# PCB_-_MODULE.net
KiCad netlist of a schematic drawn in EAGLE
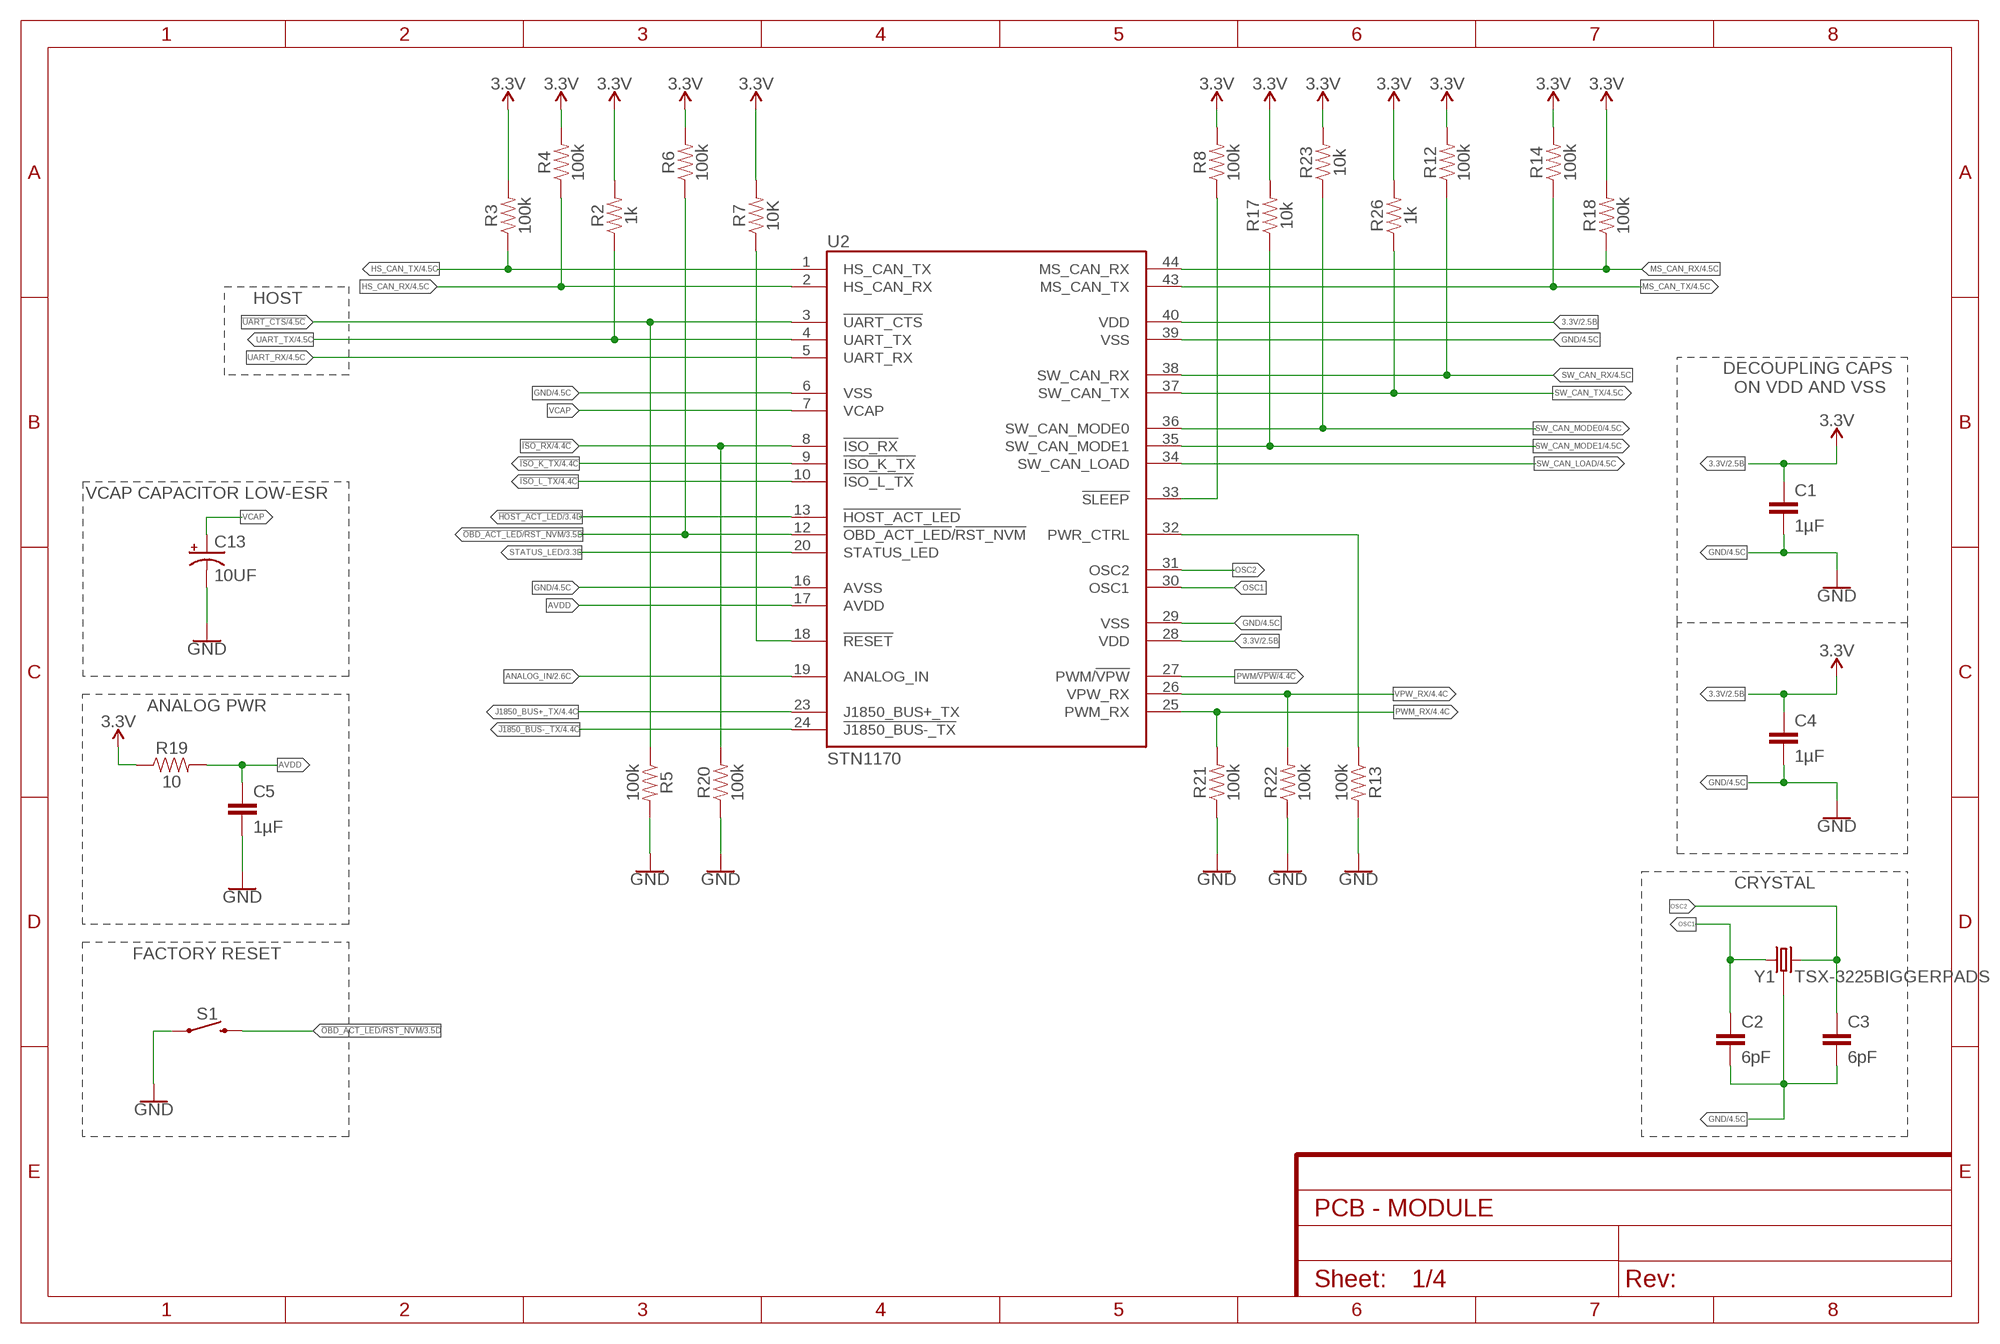
[diagram p0: schematic, sheet 1]
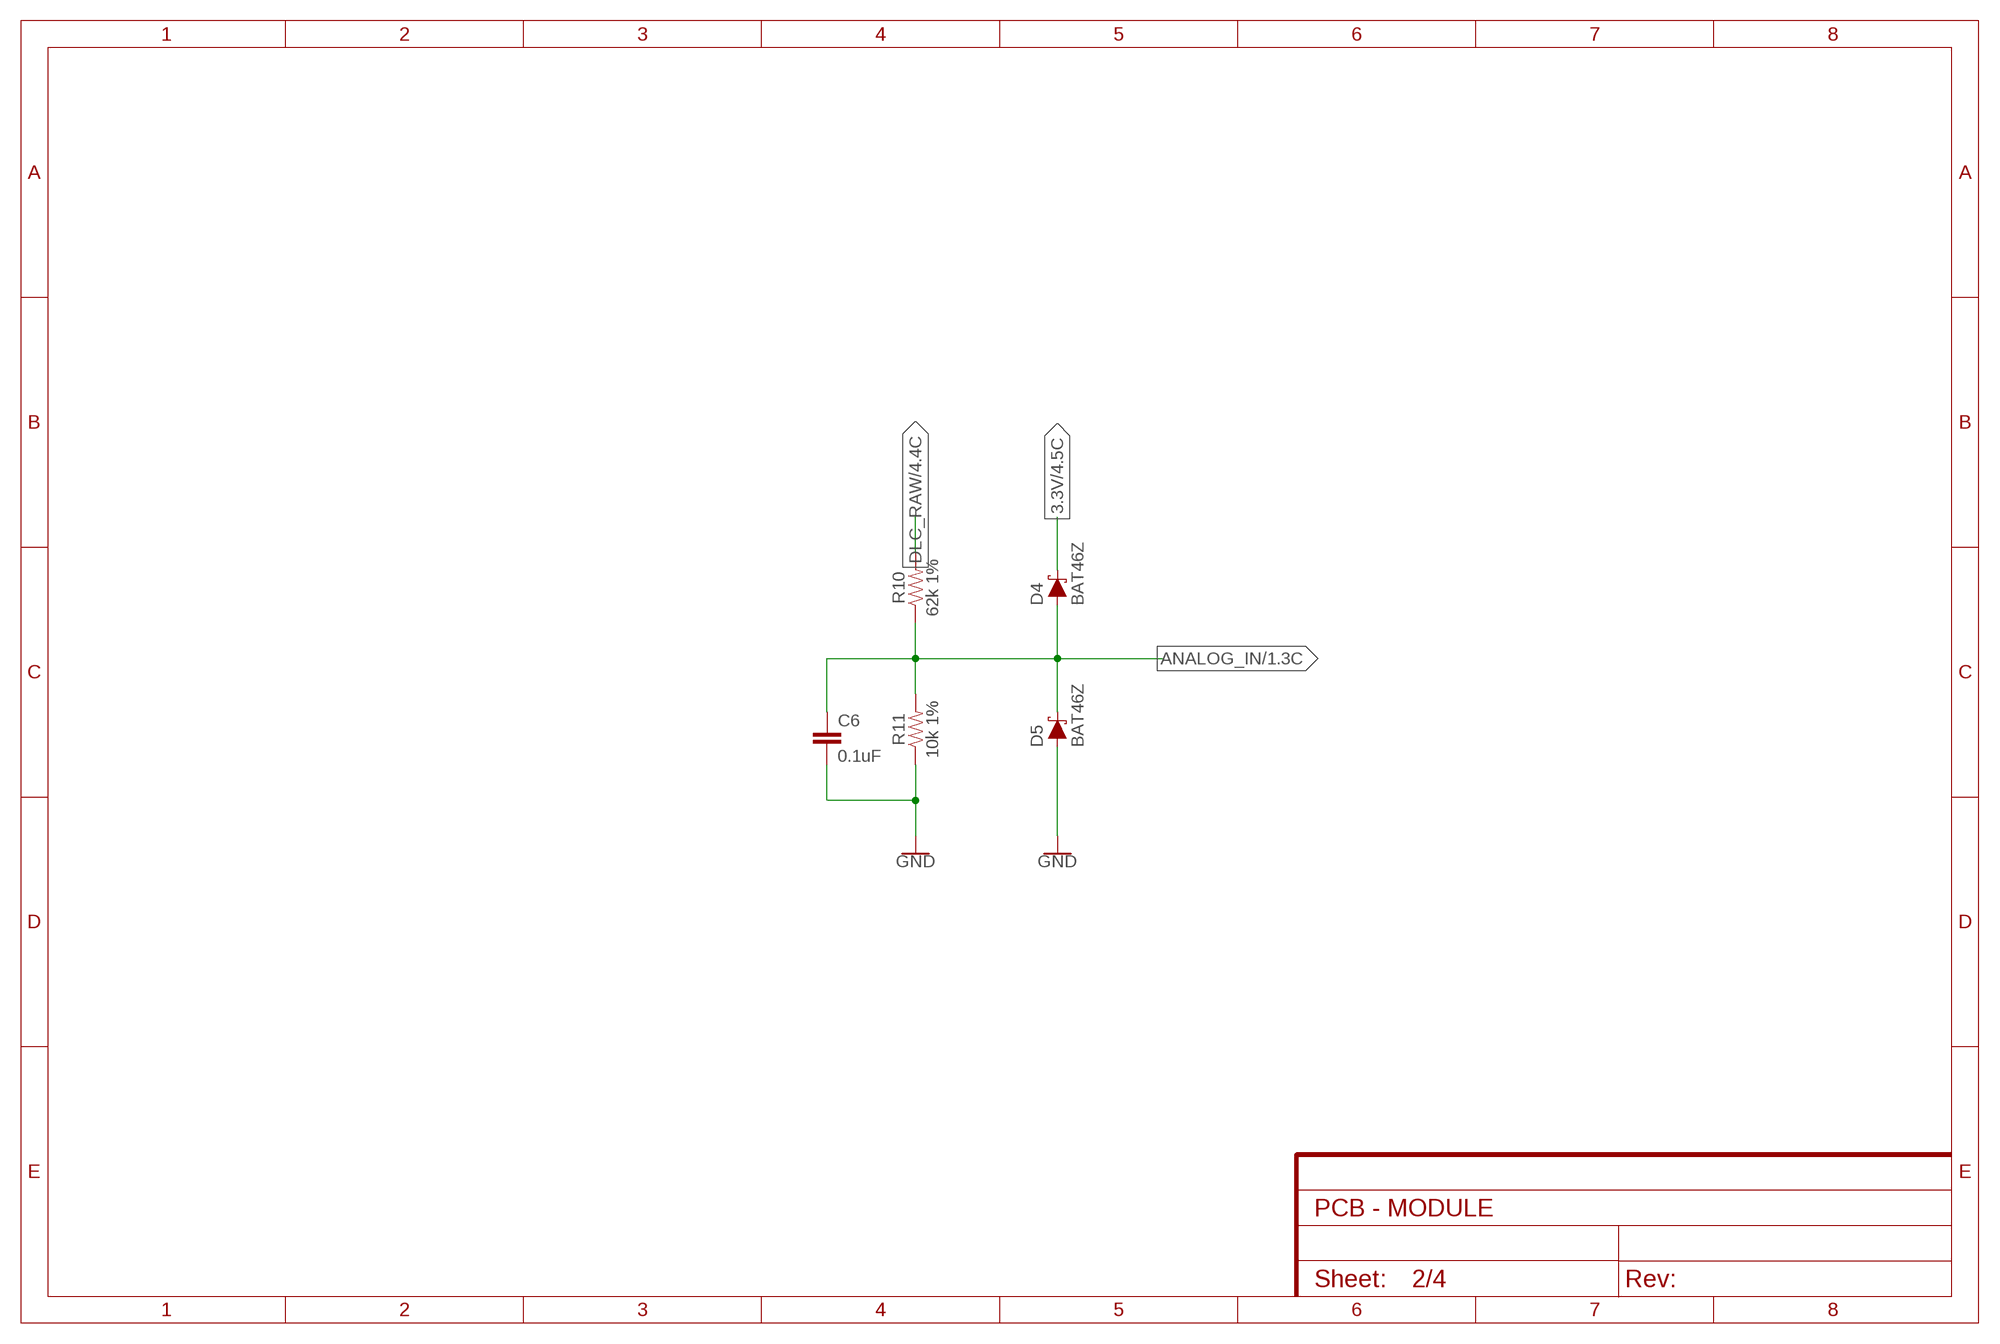
[diagram p1: schematic, sheet 2]
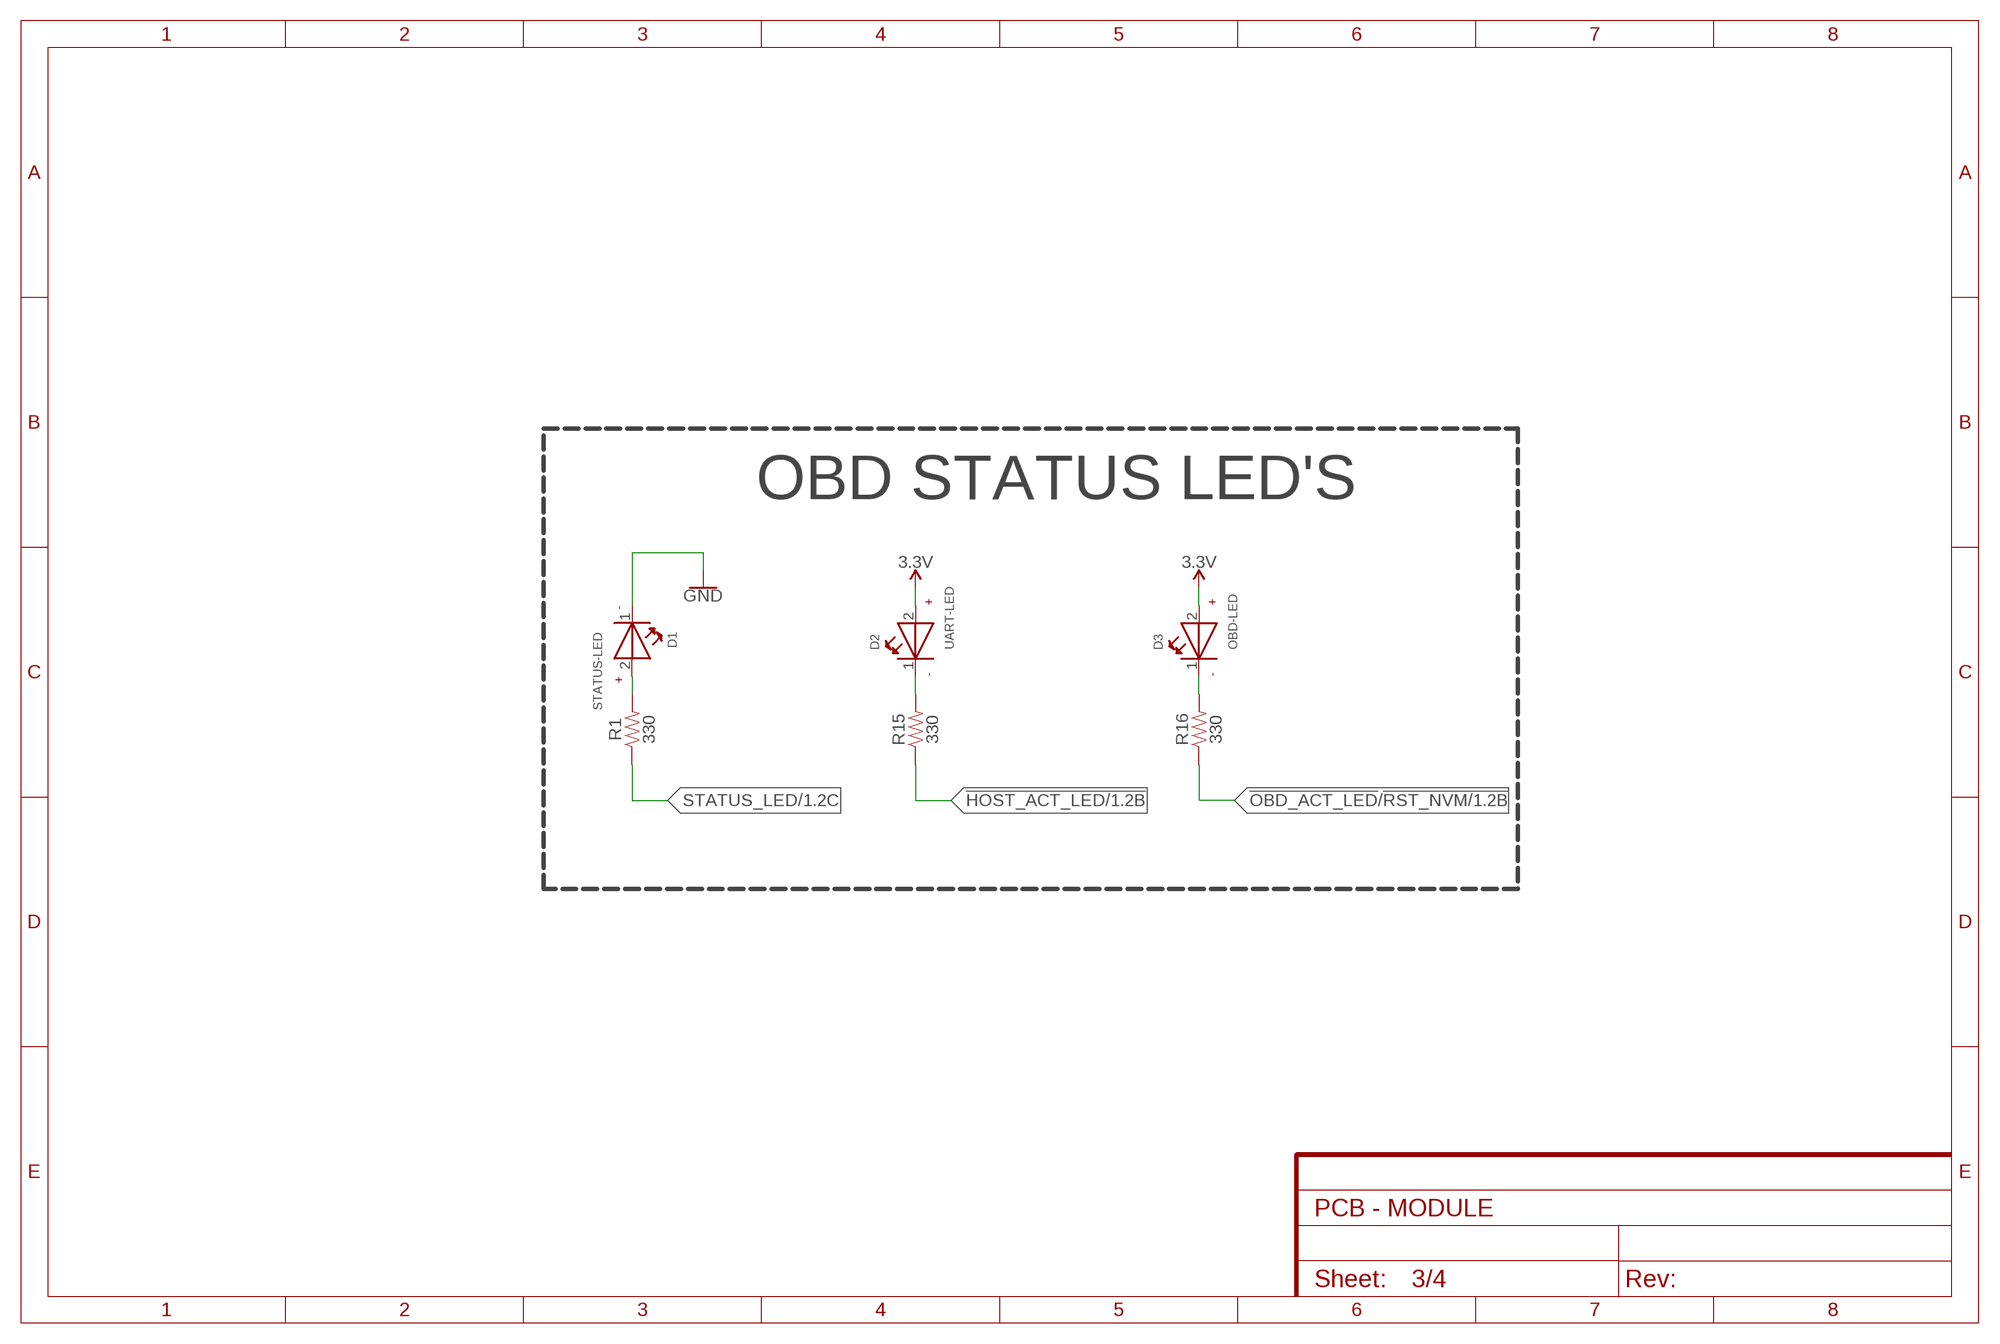
[diagram p2: schematic, sheet 3]
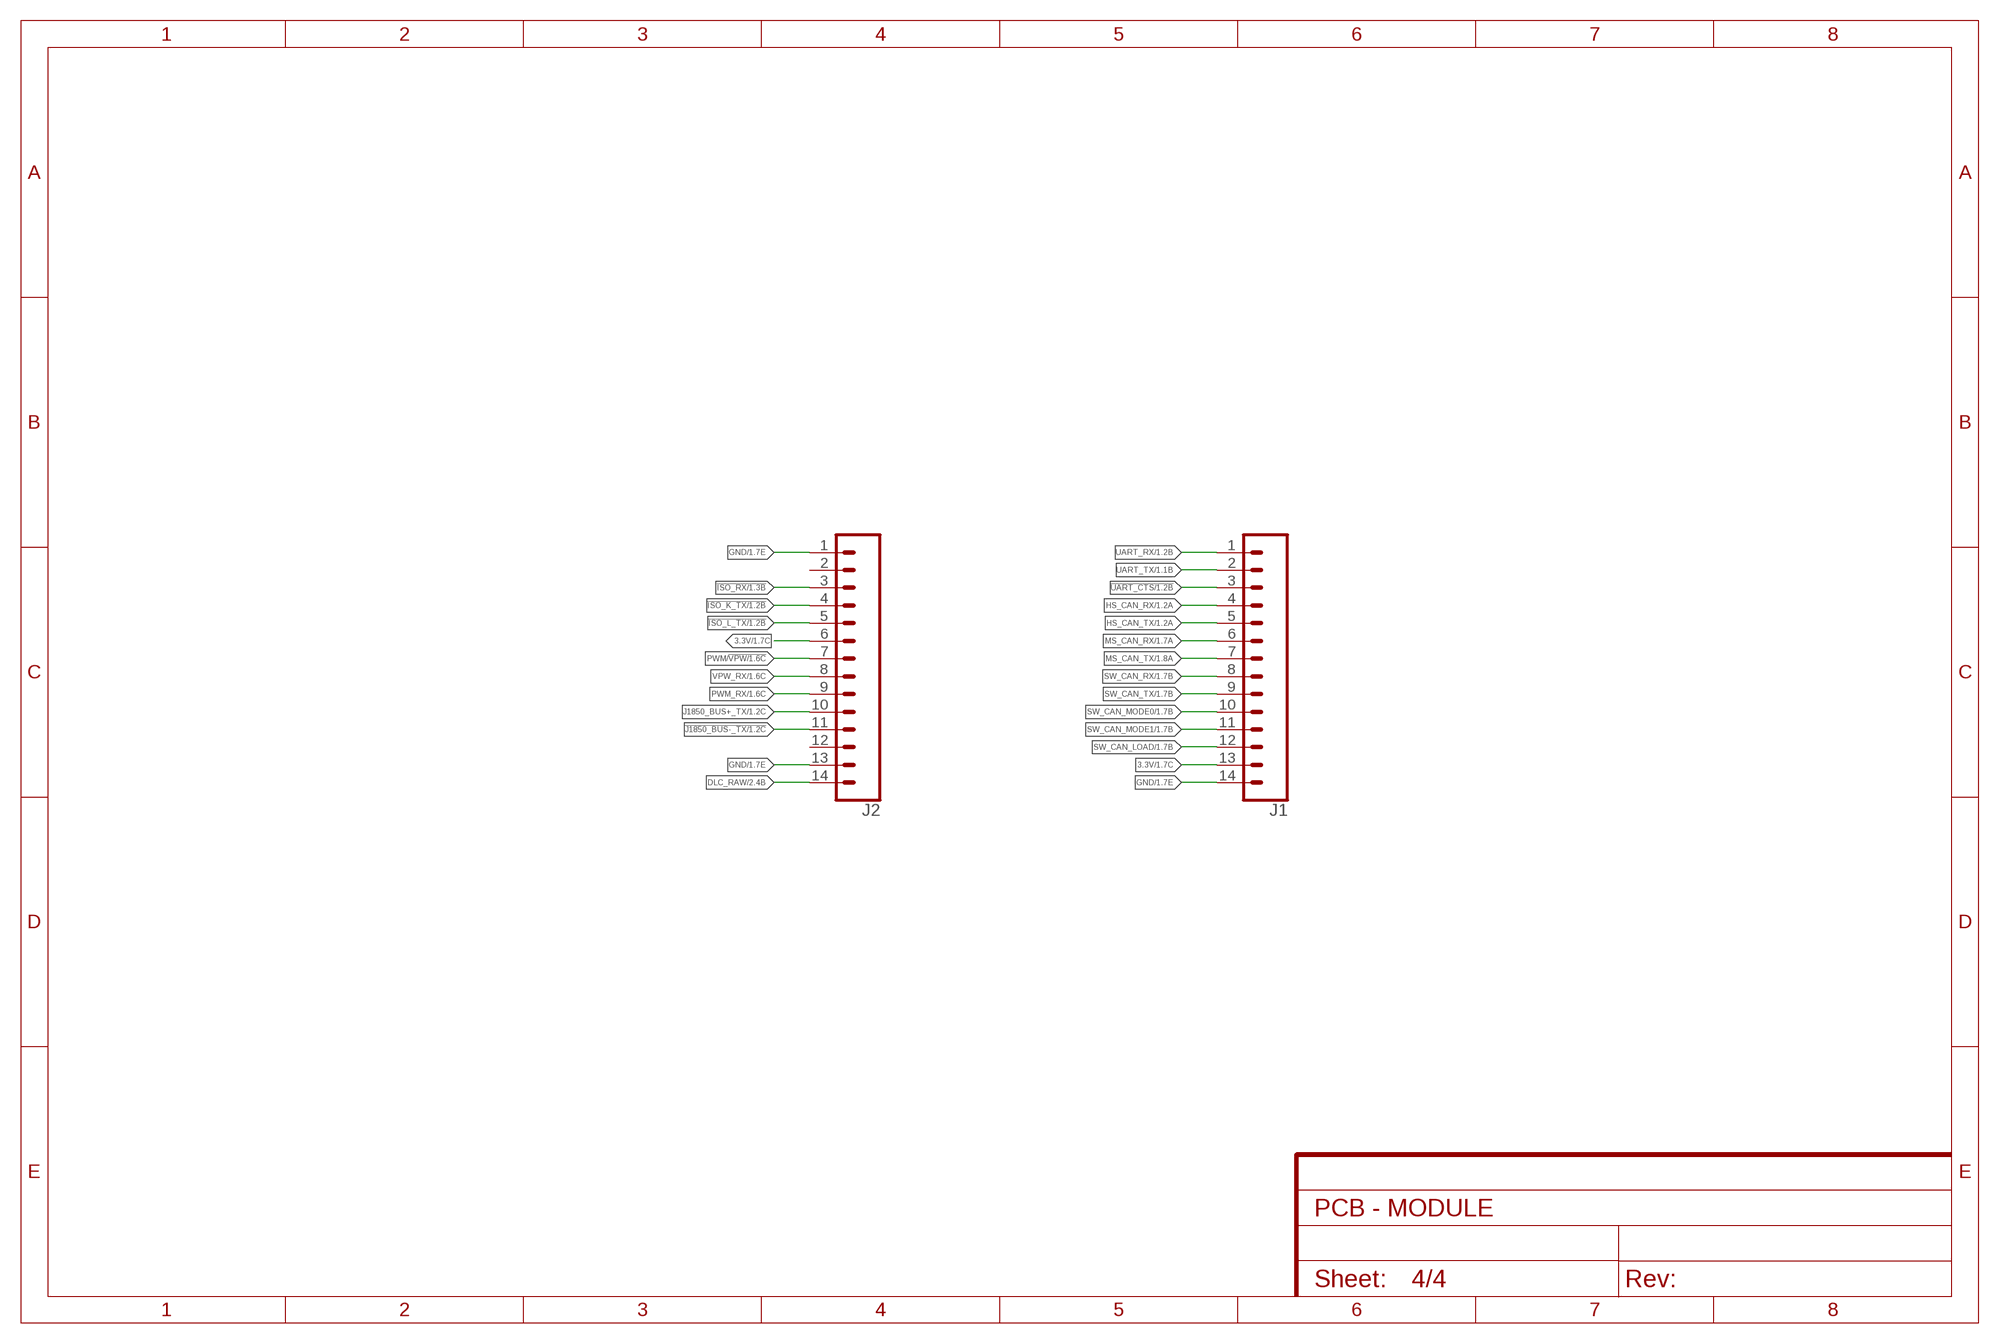
[diagram p3: schematic, sheet 4]

(export (version "E")
  (design (tool "Eeschema 10.0.6"))
  (components
    (comp (ref "C6")
      (value "0.1uF")
      (footprint "eagle-import:0805")
      (libsource (lib "eagle-import") (part "0.33UF/330NF-0805-50V-10%"))
    )
    (comp (ref "D4")
      (value "BAT46Z")
      (footprint "eagle-import:SOD-123")
      (libsource (lib "eagle-import") (part "BAT46Z"))
    )
    (comp (ref "D5")
      (value "BAT46Z")
      (footprint "eagle-import:SOD-123")
      (libsource (lib "eagle-import") (part "BAT46Z"))
    )
    (comp (ref "R10")
      (value "62k 1%")
      (footprint "eagle-import:0805")
      (libsource (lib "eagle-import") (part "0.75OHM-0805-1/4W-1%"))
    )
    (comp (ref "R11")
      (value "10k 1%")
      (footprint "eagle-import:0805")
      (libsource (lib "eagle-import") (part "0.75OHM-0805-1/4W-1%"))
    )
    (comp (ref "D1")
      (value "STATUS-LED")
      (footprint "eagle-import:WL-SMCW_1206")
      (libsource (lib "eagle-import") (part "WL-SMCW-150120RS75000-R"))
    )
    (comp (ref "D2")
      (value "UART-LED")
      (footprint "eagle-import:WL-SMCW_1206")
      (libsource (lib "eagle-import") (part "WL-SMCW-150120YS75000-Y"))
    )
    (comp (ref "D3")
      (value "OBD-LED")
      (footprint "eagle-import:WL-SMCW_1206")
      (libsource (lib "eagle-import") (part "WL-SMCW-150120GS75000-G"))
    )
    (comp (ref "R1")
      (value "330")
      (footprint "eagle-import:0805")
      (libsource (lib "eagle-import") (part "0.75OHM-0805-1/4W-1%"))
    )
    (comp (ref "R15")
      (value "330")
      (footprint "eagle-import:0805")
      (libsource (lib "eagle-import") (part "0.75OHM-0805-1/4W-1%"))
    )
    (comp (ref "R16")
      (value "330")
      (footprint "eagle-import:0805")
      (libsource (lib "eagle-import") (part "0.75OHM-0805-1/4W-1%"))
    )
    (comp (ref "J1")
      (value "CONN_14")
      (footprint "eagle-import:1X14")
      (libsource (lib "eagle-import") (part "CONN_14"))
    )
    (comp (ref "J2")
      (value "CONN_14")
      (footprint "eagle-import:1X14")
      (libsource (lib "eagle-import") (part "CONN_14"))
    )
    (comp (ref "C1")
      (value "1µF")
      (footprint "eagle-import:0805")
      (libsource (lib "eagle-import") (part "0.33UF/330NF-0805-50V-10%"))
    )
    (comp (ref "C2")
      (value "6pF")
      (footprint "eagle-import:0805")
      (libsource (lib "eagle-import") (part "0.33UF/330NF-0805-50V-10%"))
    )
    (comp (ref "C3")
      (value "6pF")
      (footprint "eagle-import:0805")
      (libsource (lib "eagle-import") (part "0.33UF/330NF-0805-50V-10%"))
    )
    (comp (ref "C4")
      (value "1µF")
      (footprint "eagle-import:0805")
      (libsource (lib "eagle-import") (part "0.33UF/330NF-0805-50V-10%"))
    )
    (comp (ref "C5")
      (value "1µF")
      (footprint "eagle-import:0805")
      (libsource (lib "eagle-import") (part "0.33UF/330NF-0805-50V-10%"))
    )
    (comp (ref "C13")
      (value "10UF")
      (footprint "eagle-import:1206")
      (libsource (lib "eagle-import") (part "10UF"))
    )
    (comp (ref "R2")
      (value "1k")
      (footprint "eagle-import:0805")
      (libsource (lib "eagle-import") (part "0.75OHM-0805-1/4W-1%"))
    )
    (comp (ref "R3")
      (value "100k")
      (footprint "eagle-import:0805")
      (libsource (lib "eagle-import") (part "0.75OHM-0805-1/4W-1%"))
    )
    (comp (ref "R4")
      (value "100k")
      (footprint "eagle-import:0805")
      (libsource (lib "eagle-import") (part "0.75OHM-0805-1/4W-1%"))
    )
    (comp (ref "R5")
      (value "100k")
      (footprint "eagle-import:0805")
      (libsource (lib "eagle-import") (part "0.75OHM-0805-1/4W-1%"))
    )
    (comp (ref "R6")
      (value "100k")
      (footprint "eagle-import:0805")
      (libsource (lib "eagle-import") (part "0.75OHM-0805-1/4W-1%"))
    )
    (comp (ref "R7")
      (value "10K")
      (footprint "eagle-import:0805")
      (libsource (lib "eagle-import") (part "0.75OHM-0805-1/4W-1%"))
    )
    (comp (ref "R8")
      (value "100k")
      (footprint "eagle-import:0805")
      (libsource (lib "eagle-import") (part "0.75OHM-0805-1/4W-1%"))
    )
    (comp (ref "R12")
      (value "100k")
      (footprint "eagle-import:0805")
      (libsource (lib "eagle-import") (part "0.75OHM-0805-1/4W-1%"))
    )
    (comp (ref "R13")
      (value "100k")
      (footprint "eagle-import:0805")
      (libsource (lib "eagle-import") (part "0.75OHM-0805-1/4W-1%"))
    )
    (comp (ref "R14")
      (value "100k")
      (footprint "eagle-import:0805")
      (libsource (lib "eagle-import") (part "0.75OHM-0805-1/4W-1%"))
    )
    (comp (ref "R17")
      (value "10k")
      (footprint "eagle-import:0805")
      (libsource (lib "eagle-import") (part "0.75OHM-0805-1/4W-1%"))
    )
    (comp (ref "R18")
      (value "100k")
      (footprint "eagle-import:0805")
      (libsource (lib "eagle-import") (part "0.75OHM-0805-1/4W-1%"))
    )
    (comp (ref "R19")
      (value "10")
      (footprint "eagle-import:0805")
      (libsource (lib "eagle-import") (part "0.75OHM-0805-1/4W-1%"))
    )
    (comp (ref "R20")
      (value "100k")
      (footprint "eagle-import:0805")
      (libsource (lib "eagle-import") (part "0.75OHM-0805-1/4W-1%"))
    )
    (comp (ref "R21")
      (value "100k")
      (footprint "eagle-import:0805")
      (libsource (lib "eagle-import") (part "0.75OHM-0805-1/4W-1%"))
    )
    (comp (ref "R22")
      (value "100k")
      (footprint "eagle-import:0805")
      (libsource (lib "eagle-import") (part "0.75OHM-0805-1/4W-1%"))
    )
    (comp (ref "R23")
      (value "10k")
      (footprint "eagle-import:0805")
      (libsource (lib "eagle-import") (part "0.75OHM-0805-1/4W-1%"))
    )
    (comp (ref "R26")
      (value "1k")
      (footprint "eagle-import:0805")
      (libsource (lib "eagle-import") (part "0.75OHM-0805-1/4W-1%"))
    )
    (comp (ref "S1")
      (value "B3U")
      (footprint "eagle-import:B3U-WO-GT-WO-B")
      (libsource (lib "eagle-import") (part "B3U"))
    )
    (comp (ref "U2")
      (value "STN1170")
      (footprint "eagle-import:TQFP44")
      (libsource (lib "eagle-import") (part "STN1170"))
    )
    (comp (ref "Y1")
      (value "TSX-3225BIGGERPADS")
      (footprint "eagle-import:TSX-3225-SOLDERING-IRON")
      (libsource (lib "eagle-import") (part "TSX-3225BIGGERPADS"))
    )
  )
  (nets
    (net (code "1") (name "3.3V") (class "Default")
      (node (ref "C1") (pin "1") (pinfunction "1_1") (pintype "passive"))
      (node (ref "C4") (pin "1") (pinfunction "1_1") (pintype "passive"))
      (node (ref "D2") (pin "2") (pinfunction "+_2") (pintype "passive"))
      (node (ref "D3") (pin "2") (pinfunction "+_2") (pintype "passive"))
      (node (ref "D4") (pin "C") (pinfunction "C_C") (pintype "passive"))
      (node (ref "J1") (pin "13") (pinfunction "13_13") (pintype "passive"))
      (node (ref "J2") (pin "6") (pinfunction "6_6") (pintype "passive"))
      (node (ref "R12") (pin "2") (pinfunction "2_2") (pintype "passive"))
      (node (ref "R14") (pin "2") (pinfunction "2_2") (pintype "passive"))
      (node (ref "R17") (pin "2") (pinfunction "2_2") (pintype "passive"))
      (node (ref "R18") (pin "2") (pinfunction "2_2") (pintype "passive"))
      (node (ref "R19") (pin "1") (pinfunction "1_1") (pintype "passive"))
      (node (ref "R2") (pin "2") (pinfunction "2_2") (pintype "passive"))
      (node (ref "R23") (pin "2") (pinfunction "2_2") (pintype "passive"))
      (node (ref "R26") (pin "2") (pinfunction "2_2") (pintype "passive"))
      (node (ref "R3") (pin "2") (pinfunction "2_2") (pintype "passive"))
      (node (ref "R4") (pin "2") (pinfunction "2_2") (pintype "passive"))
      (node (ref "R6") (pin "2") (pinfunction "2_2") (pintype "passive"))
      (node (ref "R7") (pin "2") (pinfunction "2_2") (pintype "passive"))
      (node (ref "R8") (pin "2") (pinfunction "2_2") (pintype "passive"))
      (node (ref "U2") (pin "28") (pinfunction "VDD_28") (pintype "power_in"))
      (node (ref "U2") (pin "40") (pinfunction "VDD_40") (pintype "power_in"))
    )
    (net (code "2") (name "ANALOG_IN") (class "Default")
      (node (ref "C6") (pin "1") (pinfunction "1_1") (pintype "passive"))
      (node (ref "D4") (pin "A") (pinfunction "A_A") (pintype "passive"))
      (node (ref "D5") (pin "C") (pinfunction "C_C") (pintype "passive"))
      (node (ref "R10") (pin "1") (pinfunction "1_1") (pintype "passive"))
      (node (ref "R11") (pin "2") (pinfunction "2_2") (pintype "passive"))
      (node (ref "U2") (pin "19") (pinfunction "ANALOG_IN_19") (pintype "input"))
    )
    (net (code "3") (name "AVDD") (class "Default")
      (node (ref "C5") (pin "1") (pinfunction "1_1") (pintype "passive"))
      (node (ref "R19") (pin "2") (pinfunction "2_2") (pintype "passive"))
      (node (ref "U2") (pin "17") (pinfunction "AVDD_17") (pintype "power_in"))
    )
    (net (code "4") (name "DLC_RAW") (class "Default")
      (node (ref "J2") (pin "14") (pinfunction "14_14") (pintype "passive"))
      (node (ref "R10") (pin "2") (pinfunction "2_2") (pintype "passive"))
    )
    (net (code "5") (name "GND") (class "Default")
      (node (ref "C1") (pin "2") (pinfunction "2_2") (pintype "passive"))
      (node (ref "C13") (pin "2") (pinfunction "-_2") (pintype "passive"))
      (node (ref "C2") (pin "2") (pinfunction "2_2") (pintype "passive"))
      (node (ref "C3") (pin "2") (pinfunction "2_2") (pintype "passive"))
      (node (ref "C4") (pin "2") (pinfunction "2_2") (pintype "passive"))
      (node (ref "C5") (pin "2") (pinfunction "2_2") (pintype "passive"))
      (node (ref "C6") (pin "2") (pinfunction "2_2") (pintype "passive"))
      (node (ref "D1") (pin "1") (pinfunction "-_1") (pintype "passive"))
      (node (ref "D5") (pin "A") (pinfunction "A_A") (pintype "passive"))
      (node (ref "J1") (pin "14") (pinfunction "14_14") (pintype "passive"))
      (node (ref "J2") (pin "1") (pinfunction "1_1") (pintype "passive"))
      (node (ref "J2") (pin "13") (pinfunction "13_13") (pintype "passive"))
      (node (ref "R11") (pin "1") (pinfunction "1_1") (pintype "passive"))
      (node (ref "R13") (pin "2") (pinfunction "2_2") (pintype "passive"))
      (node (ref "R20") (pin "1") (pinfunction "1_1") (pintype "passive"))
      (node (ref "R21") (pin "1") (pinfunction "1_1") (pintype "passive"))
      (node (ref "R22") (pin "1") (pinfunction "1_1") (pintype "passive"))
      (node (ref "R5") (pin "2") (pinfunction "2_2") (pintype "passive"))
      (node (ref "S1") (pin "1") (pinfunction "1_1") (pintype "passive"))
      (node (ref "U2") (pin "16") (pinfunction "AVSS_16") (pintype "power_in"))
      (node (ref "U2") (pin "29") (pinfunction "VSS_29") (pintype "power_in"))
      (node (ref "U2") (pin "39") (pinfunction "VSS_39") (pintype "power_in"))
      (node (ref "U2") (pin "6") (pinfunction "VSS_6") (pintype "power_in"))
      (node (ref "Y1") (pin "2") (pinfunction "3_2") (pintype "passive"))
      (node (ref "Y1") (pin "4") (pinfunction "3_4") (pintype "passive"))
    )
    (net (code "6") (name "HS_CAN_RX") (class "Default")
      (node (ref "J1") (pin "4") (pinfunction "4_4") (pintype "passive"))
      (node (ref "R4") (pin "1") (pinfunction "1_1") (pintype "passive"))
      (node (ref "U2") (pin "2") (pinfunction "HS_CAN_RX_2") (pintype "input"))
    )
    (net (code "7") (name "HS_CAN_TX") (class "Default")
      (node (ref "J1") (pin "5") (pinfunction "5_5") (pintype "passive"))
      (node (ref "R3") (pin "1") (pinfunction "1_1") (pintype "passive"))
      (node (ref "U2") (pin "1") (pinfunction "HS_CAN_TX_1") (pintype "input"))
    )
    (net (code "8") (name "J1850_BUS+_TX") (class "Default")
      (node (ref "J2") (pin "10") (pinfunction "10_10") (pintype "passive"))
      (node (ref "U2") (pin "23") (pinfunction "J1850_BUS+_TX_23") (pintype "output"))
    )
    (net (code "9") (name "MS_CAN_RX") (class "Default")
      (node (ref "J1") (pin "6") (pinfunction "6_6") (pintype "passive"))
      (node (ref "R18") (pin "1") (pinfunction "1_1") (pintype "passive"))
      (node (ref "U2") (pin "44") (pinfunction "MS_CAN_RX_44") (pintype "input"))
    )
    (net (code "10") (name "MS_CAN_TX") (class "Default")
      (node (ref "J1") (pin "7") (pinfunction "7_7") (pintype "passive"))
      (node (ref "R14") (pin "1") (pinfunction "1_1") (pintype "passive"))
      (node (ref "U2") (pin "43") (pinfunction "MS_CAN_TX_43") (pintype "output"))
    )
    (net (code "11") (name "Net-(D1-+)") (class "Default")
      (node (ref "D1") (pin "2") (pinfunction "+_2") (pintype "passive"))
      (node (ref "R1") (pin "2") (pinfunction "2_2") (pintype "passive"))
    )
    (net (code "12") (name "Net-(D2--)") (class "Default")
      (node (ref "D2") (pin "1") (pinfunction "-_1") (pintype "passive"))
      (node (ref "R15") (pin "2") (pinfunction "2_2") (pintype "passive"))
    )
    (net (code "13") (name "Net-(D3--)") (class "Default")
      (node (ref "D3") (pin "1") (pinfunction "-_1") (pintype "passive"))
      (node (ref "R16") (pin "2") (pinfunction "2_2") (pintype "passive"))
    )
    (net (code "14") (name "Net-(U2-PWR_CTRL)") (class "Default")
      (node (ref "R13") (pin "1") (pinfunction "1_1") (pintype "passive"))
      (node (ref "U2") (pin "32") (pinfunction "PWR_CTRL_32") (pintype "output"))
    )
    (net (code "15") (name "Net-(U2-~{RESET})") (class "Default")
      (node (ref "R7") (pin "1") (pinfunction "1_1") (pintype "passive"))
      (node (ref "U2") (pin "18") (pinfunction "~{RESET}_18") (pintype "input"))
    )
    (net (code "16") (name "Net-(U2-~{SLEEP})") (class "Default")
      (node (ref "R8") (pin "1") (pinfunction "1_1") (pintype "passive"))
      (node (ref "U2") (pin "33") (pinfunction "~{SLEEP}_33") (pintype "input"))
    )
    (net (code "17") (name "OSC1") (class "Default")
      (node (ref "C2") (pin "1") (pinfunction "1_1") (pintype "passive"))
      (node (ref "U2") (pin "30") (pinfunction "OSC1_30") (pintype "input"))
      (node (ref "Y1") (pin "1") (pinfunction "1_1") (pintype "passive"))
    )
    (net (code "18") (name "OSC2") (class "Default")
      (node (ref "C3") (pin "1") (pinfunction "1_1") (pintype "passive"))
      (node (ref "U2") (pin "31") (pinfunction "OSC2_31") (pintype "output"))
      (node (ref "Y1") (pin "3") (pinfunction "2_3") (pintype "passive"))
    )
    (net (code "19") (name "PWM_RX") (class "Default")
      (node (ref "J2") (pin "9") (pinfunction "9_9") (pintype "passive"))
      (node (ref "R21") (pin "2") (pinfunction "2_2") (pintype "passive"))
      (node (ref "U2") (pin "25") (pinfunction "PWM_RX_25") (pintype "input"))
    )
    (net (code "20") (name "PWM{slash}~{VPW}") (class "Default")
      (node (ref "J2") (pin "7") (pinfunction "7_7") (pintype "passive"))
      (node (ref "U2") (pin "27") (pinfunction "PWM/~{VPW}_27") (pintype "output"))
    )
    (net (code "21") (name "STATUS_LED") (class "Default")
      (node (ref "R1") (pin "1") (pinfunction "1_1") (pintype "passive"))
      (node (ref "U2") (pin "20") (pinfunction "STATUS_LED_20") (pintype "output"))
    )
    (net (code "22") (name "SW_CAN_LOAD") (class "Default")
      (node (ref "J1") (pin "12") (pinfunction "12_12") (pintype "passive"))
      (node (ref "U2") (pin "34") (pinfunction "SW_CAN_LOAD_34") (pintype "output"))
    )
    (net (code "23") (name "SW_CAN_MODE0") (class "Default")
      (node (ref "J1") (pin "10") (pinfunction "10_10") (pintype "passive"))
      (node (ref "R23") (pin "1") (pinfunction "1_1") (pintype "passive"))
      (node (ref "U2") (pin "36") (pinfunction "SW_CAN_MODE0_36") (pintype "output"))
    )
    (net (code "24") (name "SW_CAN_MODE1") (class "Default")
      (node (ref "J1") (pin "11") (pinfunction "11_11") (pintype "passive"))
      (node (ref "R17") (pin "1") (pinfunction "1_1") (pintype "passive"))
      (node (ref "U2") (pin "35") (pinfunction "SW_CAN_MODE1_35") (pintype "output"))
    )
    (net (code "25") (name "SW_CAN_RX") (class "Default")
      (node (ref "J1") (pin "8") (pinfunction "8_8") (pintype "passive"))
      (node (ref "R12") (pin "1") (pinfunction "1_1") (pintype "passive"))
      (node (ref "U2") (pin "38") (pinfunction "SW_CAN_RX_38") (pintype "input"))
    )
    (net (code "26") (name "SW_CAN_TX") (class "Default")
      (node (ref "J1") (pin "9") (pinfunction "9_9") (pintype "passive"))
      (node (ref "R26") (pin "1") (pinfunction "1_1") (pintype "passive"))
      (node (ref "U2") (pin "37") (pinfunction "SW_CAN_TX_37") (pintype "output"))
    )
    (net (code "27") (name "UART_RX") (class "Default")
      (node (ref "J1") (pin "1") (pinfunction "1_1") (pintype "passive"))
      (node (ref "U2") (pin "5") (pinfunction "UART_RX_5") (pintype "input"))
    )
    (net (code "28") (name "UART_TX") (class "Default")
      (node (ref "J1") (pin "2") (pinfunction "2_2") (pintype "passive"))
      (node (ref "R2") (pin "1") (pinfunction "1_1") (pintype "passive"))
      (node (ref "U2") (pin "4") (pinfunction "UART_TX_4") (pintype "output"))
    )
    (net (code "29") (name "VCAP") (class "Default")
      (node (ref "C13") (pin "1") (pinfunction "+_1") (pintype "passive"))
      (node (ref "U2") (pin "7") (pinfunction "VCAP_7") (pintype "power_in"))
    )
    (net (code "30") (name "VPW_RX") (class "Default")
      (node (ref "J2") (pin "8") (pinfunction "8_8") (pintype "passive"))
      (node (ref "R22") (pin "2") (pinfunction "2_2") (pintype "passive"))
      (node (ref "U2") (pin "26") (pinfunction "VPW_RX_26") (pintype "input"))
    )
    (net (code "31") (name "unconnected-(J2-Pad2)") (class "Default")
      (node (ref "J2") (pin "2") (pinfunction "2_2") (pintype "passive"))
    )
    (net (code "32") (name "unconnected-(J2-Pad12)") (class "Default")
      (node (ref "J2") (pin "12") (pinfunction "12_12") (pintype "passive"))
    )
    (net (code "33") (name "~{HOST_ACT_LED}") (class "Default")
      (node (ref "R15") (pin "1") (pinfunction "1_1") (pintype "passive"))
      (node (ref "U2") (pin "13") (pinfunction "~{HOST_ACT_LED}_13") (pintype "output"))
    )
    (net (code "34") (name "~{ISO_K_TX}") (class "Default")
      (node (ref "J2") (pin "4") (pinfunction "4_4") (pintype "passive"))
      (node (ref "U2") (pin "9") (pinfunction "~{ISO_K_TX}_9") (pintype "output"))
    )
    (net (code "35") (name "~{ISO_L_TX}") (class "Default")
      (node (ref "J2") (pin "5") (pinfunction "5_5") (pintype "passive"))
      (node (ref "U2") (pin "10") (pinfunction "~{ISO_L_TX}_10") (pintype "output"))
    )
    (net (code "36") (name "~{ISO_RX}") (class "Default")
      (node (ref "J2") (pin "3") (pinfunction "3_3") (pintype "passive"))
      (node (ref "R20") (pin "2") (pinfunction "2_2") (pintype "passive"))
      (node (ref "U2") (pin "8") (pinfunction "~{ISO_RX}_8") (pintype "input"))
    )
    (net (code "37") (name "~{J1850_BUS-_TX}") (class "Default")
      (node (ref "J2") (pin "11") (pinfunction "11_11") (pintype "passive"))
      (node (ref "U2") (pin "24") (pinfunction "~{J1850_BUS-_TX}_24") (pintype "output"))
    )
    (net (code "38") (name "~{OBD_ACT_LED}{slash}~{RST_NVM}") (class "Default")
      (node (ref "R16") (pin "1") (pinfunction "1_1") (pintype "passive"))
      (node (ref "R6") (pin "1") (pinfunction "1_1") (pintype "passive"))
      (node (ref "S1") (pin "2") (pinfunction "2_2") (pintype "passive"))
      (node (ref "U2") (pin "12") (pinfunction "~{OBD_ACT_LED}/~{RST_NVM}_12") (pintype "output"))
    )
    (net (code "39") (name "~{UART_CTS}") (class "Default")
      (node (ref "J1") (pin "3") (pinfunction "3_3") (pintype "passive"))
      (node (ref "R5") (pin "1") (pinfunction "1_1") (pintype "passive"))
      (node (ref "U2") (pin "3") (pinfunction "~{UART_CTS}_3") (pintype "input"))
    )
  )
)
